# 1750_master.net
KiCad netlist of a schematic drawn in EAGLE
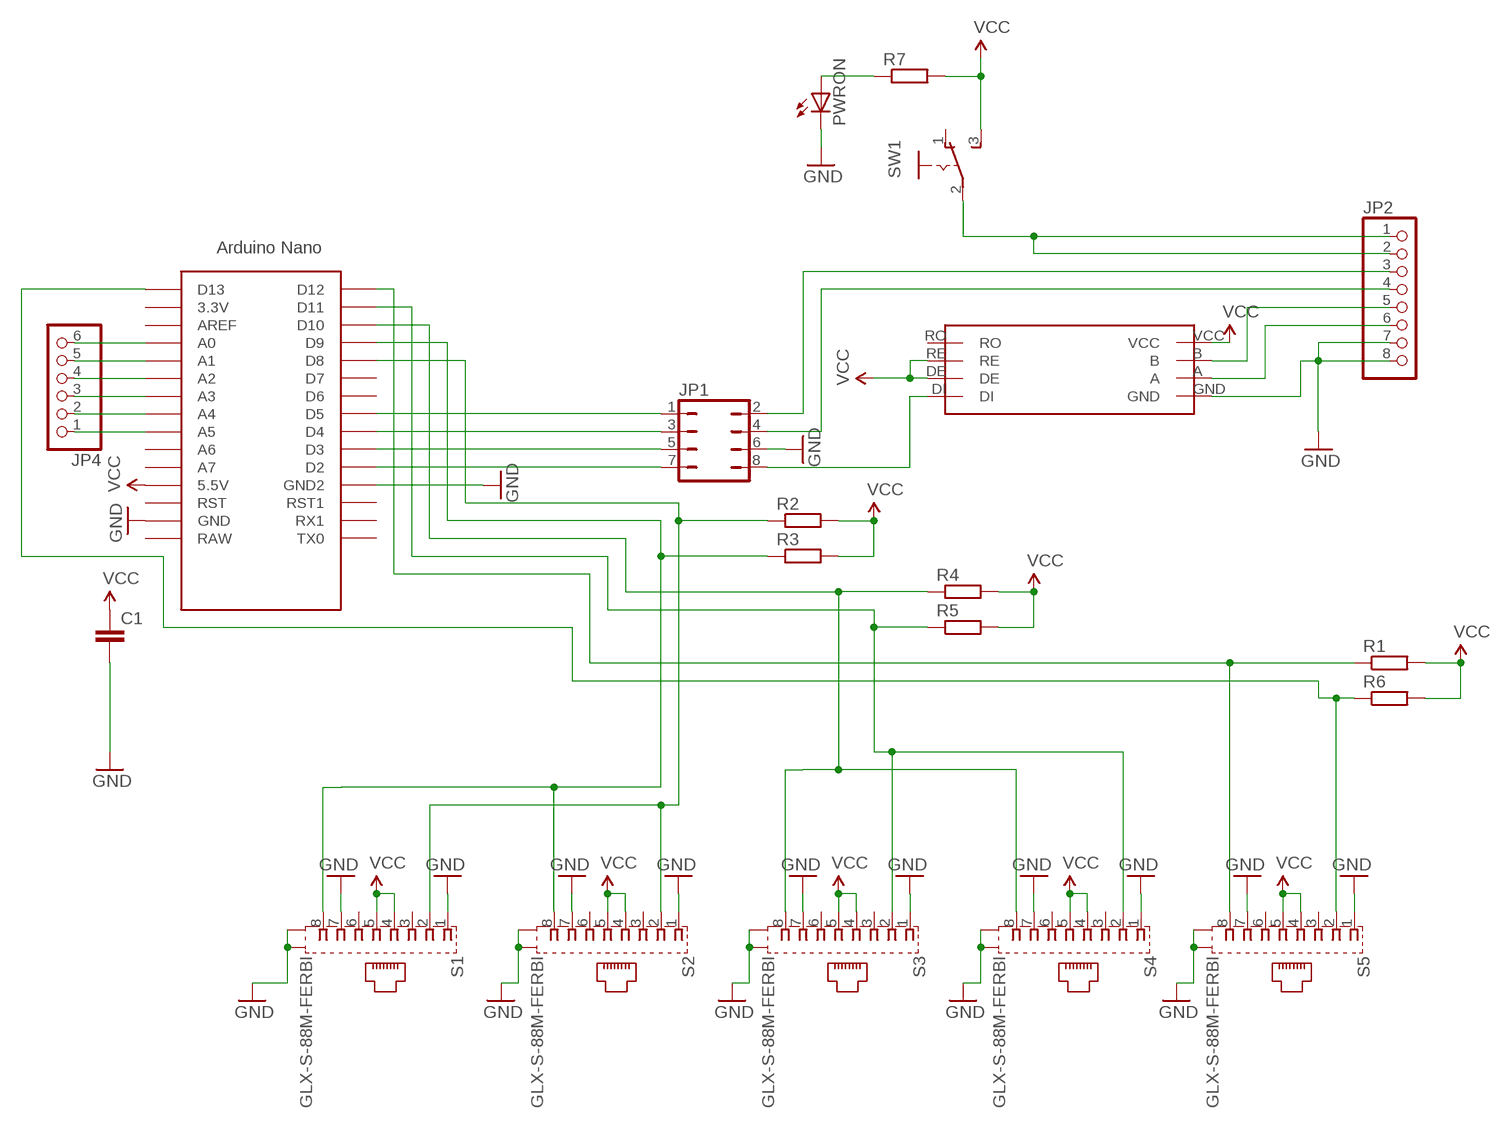
[diagram p0: schematic, sheet 1]

(export (version "E")
  (design (tool "Eeschema 10.0.6"))
  (components
    (comp (ref "C1")
      (value "C-EU025-025X050")
      (footprint "eagle-import:C025-025X050")
      (libsource (lib "eagle-import") (part "C-EU025-025X050"))
    )
    (comp (ref "JP1")
      (value "JP4Q")
      (footprint "eagle-import:JP4Q")
      (libsource (lib "eagle-import") (part "JP4Q"))
    )
    (comp (ref "JP2")
      (value "PINHD-1X8")
      (footprint "eagle-import:1X08")
      (libsource (lib "eagle-import") (part "PINHD-1X8"))
    )
    (comp (ref "JP4")
      (value "PINHD-1X6")
      (footprint "eagle-import:1X06")
      (libsource (lib "eagle-import") (part "PINHD-1X6"))
    )
    (comp (ref "PWRON")
      (value "LED5MM")
      (footprint "eagle-import:LED5MM")
      (libsource (lib "eagle-import") (part "LED5MM"))
    )
    (comp (ref "R1")
      (value "R-EU_0207/10")
      (footprint "eagle-import:0207_10")
      (libsource (lib "eagle-import") (part "R-EU_0207/10"))
    )
    (comp (ref "R2")
      (value "R-EU_0207/10")
      (footprint "eagle-import:0207_10")
      (libsource (lib "eagle-import") (part "R-EU_0207/10"))
    )
    (comp (ref "R3")
      (value "R-EU_0207/10")
      (footprint "eagle-import:0207_10")
      (libsource (lib "eagle-import") (part "R-EU_0207/10"))
    )
    (comp (ref "R4")
      (value "R-EU_0207/10")
      (footprint "eagle-import:0207_10")
      (libsource (lib "eagle-import") (part "R-EU_0207/10"))
    )
    (comp (ref "R5")
      (value "R-EU_0207/10")
      (footprint "eagle-import:0207_10")
      (libsource (lib "eagle-import") (part "R-EU_0207/10"))
    )
    (comp (ref "R6")
      (value "R-EU_0207/10")
      (footprint "eagle-import:0207_10")
      (libsource (lib "eagle-import") (part "R-EU_0207/10"))
    )
    (comp (ref "R7")
      (value "R-EU_0207/10")
      (footprint "eagle-import:0207_10")
      (libsource (lib "eagle-import") (part "R-EU_0207/10"))
    )
    (comp (ref "S1")
      (value "GLX-S-88M-FERBI")
      (footprint "eagle-import:GLX-S-88M-FERBI")
      (libsource (lib "eagle-import") (part "GLX-S-88M-FERBI"))
    )
    (comp (ref "S2")
      (value "GLX-S-88M-FERBI")
      (footprint "eagle-import:GLX-S-88M-FERBI")
      (libsource (lib "eagle-import") (part "GLX-S-88M-FERBI"))
    )
    (comp (ref "S3")
      (value "GLX-S-88M-FERBI")
      (footprint "eagle-import:GLX-S-88M-FERBI")
      (libsource (lib "eagle-import") (part "GLX-S-88M-FERBI"))
    )
    (comp (ref "S4")
      (value "GLX-S-88M-FERBI")
      (footprint "eagle-import:GLX-S-88M-FERBI")
      (libsource (lib "eagle-import") (part "GLX-S-88M-FERBI"))
    )
    (comp (ref "S5")
      (value "GLX-S-88M-FERBI")
      (footprint "eagle-import:GLX-S-88M-FERBI")
      (libsource (lib "eagle-import") (part "GLX-S-88M-FERBI"))
    )
    (comp (ref "SW1")
      (value "255SB")
      (footprint "eagle-import:255SB")
      (libsource (lib "eagle-import") (part "255SB"))
    )
    (comp (ref "U$1")
      (value "NANOF")
      (footprint "eagle-import:NANOF")
      (libsource (lib "eagle-import") (part "NANOF"))
    )
    (comp (ref "U$2")
      (value "485F")
      (footprint "eagle-import:485F")
      (libsource (lib "eagle-import") (part "485F"))
    )
  )
  (nets
    (net (code "1") (name "GND") (class "Default")
      (node (ref "C1") (pin "2") (pinfunction "2_2") (pintype "passive"))
      (node (ref "JP1") (pin "6") (pinfunction "6_6") (pintype "passive"))
      (node (ref "JP2") (pin "7") (pinfunction "7_7") (pintype "passive"))
      (node (ref "JP2") (pin "8") (pinfunction "8_8") (pintype "passive"))
      (node (ref "PWRON") (pin "K") (pinfunction "C_K") (pintype "passive"))
      (node (ref "S1") (pin "1") (pinfunction "1_1") (pintype "passive"))
      (node (ref "S1") (pin "7") (pinfunction "7_7") (pintype "passive"))
      (node (ref "S1") (pin "S1") (pinfunction "S1_S1") (pintype "passive"))
      (node (ref "S1") (pin "S2") (pinfunction "S2_S2") (pintype "passive"))
      (node (ref "S2") (pin "1") (pinfunction "1_1") (pintype "passive"))
      (node (ref "S2") (pin "7") (pinfunction "7_7") (pintype "passive"))
      (node (ref "S2") (pin "S1") (pinfunction "S1_S1") (pintype "passive"))
      (node (ref "S2") (pin "S2") (pinfunction "S2_S2") (pintype "passive"))
      (node (ref "S3") (pin "1") (pinfunction "1_1") (pintype "passive"))
      (node (ref "S3") (pin "7") (pinfunction "7_7") (pintype "passive"))
      (node (ref "S3") (pin "S1") (pinfunction "S1_S1") (pintype "passive"))
      (node (ref "S3") (pin "S2") (pinfunction "S2_S2") (pintype "passive"))
      (node (ref "S4") (pin "1") (pinfunction "1_1") (pintype "passive"))
      (node (ref "S4") (pin "7") (pinfunction "7_7") (pintype "passive"))
      (node (ref "S4") (pin "S1") (pinfunction "S1_S1") (pintype "passive"))
      (node (ref "S4") (pin "S2") (pinfunction "S2_S2") (pintype "passive"))
      (node (ref "S5") (pin "1") (pinfunction "1_1") (pintype "passive"))
      (node (ref "S5") (pin "7") (pinfunction "7_7") (pintype "passive"))
      (node (ref "S5") (pin "S1") (pinfunction "S1_S1") (pintype "passive"))
      (node (ref "S5") (pin "S2") (pinfunction "S2_S2") (pintype "passive"))
      (node (ref "U$1") (pin "GND") (pinfunction "GND_GND") (pintype "bidirectional"))
      (node (ref "U$1") (pin "GND1") (pinfunction "GND2_GND1") (pintype "bidirectional"))
      (node (ref "U$2") (pin "GND") (pinfunction "GND_GND") (pintype "power_in"))
    )
    (net (code "2") (name "Net-(JP1-Pad1)") (class "Default")
      (node (ref "JP1") (pin "1") (pinfunction "1_1") (pintype "passive"))
      (node (ref "U$1") (pin "D5") (pinfunction "D5_D5") (pintype "bidirectional"))
    )
    (net (code "3") (name "Net-(JP1-Pad2)") (class "Default")
      (node (ref "JP1") (pin "2") (pinfunction "2_2") (pintype "passive"))
      (node (ref "JP2") (pin "3") (pinfunction "3_3") (pintype "passive"))
    )
    (net (code "4") (name "Net-(JP1-Pad3)") (class "Default")
      (node (ref "JP1") (pin "3") (pinfunction "3_3") (pintype "passive"))
      (node (ref "U$1") (pin "D4") (pinfunction "D4_D4") (pintype "bidirectional"))
    )
    (net (code "5") (name "Net-(JP1-Pad4)") (class "Default")
      (node (ref "JP1") (pin "4") (pinfunction "4_4") (pintype "passive"))
      (node (ref "JP2") (pin "4") (pinfunction "4_4") (pintype "passive"))
    )
    (net (code "6") (name "Net-(JP1-Pad5)") (class "Default")
      (node (ref "JP1") (pin "5") (pinfunction "5_5") (pintype "passive"))
      (node (ref "U$1") (pin "D3") (pinfunction "D3_D3") (pintype "bidirectional"))
    )
    (net (code "7") (name "Net-(JP1-Pad7)") (class "Default")
      (node (ref "JP1") (pin "7") (pinfunction "7_7") (pintype "passive"))
      (node (ref "U$1") (pin "D2") (pinfunction "D2_D2") (pintype "bidirectional"))
    )
    (net (code "8") (name "Net-(JP1-Pad8)") (class "Default")
      (node (ref "JP1") (pin "8") (pinfunction "8_8") (pintype "passive"))
      (node (ref "U$2") (pin "DI") (pinfunction "DI_DI") (pintype "bidirectional"))
    )
    (net (code "9") (name "Net-(JP2-Pad5)") (class "Default")
      (node (ref "JP2") (pin "5") (pinfunction "5_5") (pintype "passive"))
      (node (ref "U$2") (pin "B") (pinfunction "B_B") (pintype "bidirectional"))
    )
    (net (code "10") (name "Net-(JP2-Pad6)") (class "Default")
      (node (ref "JP2") (pin "6") (pinfunction "6_6") (pintype "passive"))
      (node (ref "U$2") (pin "A") (pinfunction "A_A") (pintype "bidirectional"))
    )
    (net (code "11") (name "Net-(JP4-Pad1)") (class "Default")
      (node (ref "JP4") (pin "1") (pinfunction "1_1") (pintype "passive"))
      (node (ref "U$1") (pin "A5") (pinfunction "A5_A5") (pintype "bidirectional"))
    )
    (net (code "12") (name "Net-(JP4-Pad2)") (class "Default")
      (node (ref "JP4") (pin "2") (pinfunction "2_2") (pintype "passive"))
      (node (ref "U$1") (pin "A4") (pinfunction "A4_A4") (pintype "bidirectional"))
    )
    (net (code "13") (name "Net-(JP4-Pad3)") (class "Default")
      (node (ref "JP4") (pin "3") (pinfunction "3_3") (pintype "passive"))
      (node (ref "U$1") (pin "A3") (pinfunction "A3_A3") (pintype "bidirectional"))
    )
    (net (code "14") (name "Net-(JP4-Pad4)") (class "Default")
      (node (ref "JP4") (pin "4") (pinfunction "4_4") (pintype "passive"))
      (node (ref "U$1") (pin "A2") (pinfunction "A2_A2") (pintype "bidirectional"))
    )
    (net (code "15") (name "Net-(JP4-Pad5)") (class "Default")
      (node (ref "JP4") (pin "5") (pinfunction "5_5") (pintype "passive"))
      (node (ref "U$1") (pin "A1") (pinfunction "A1_A1") (pintype "bidirectional"))
    )
    (net (code "16") (name "Net-(JP4-Pad6)") (class "Default")
      (node (ref "JP4") (pin "6") (pinfunction "6_6") (pintype "passive"))
      (node (ref "U$1") (pin "A0") (pinfunction "A0_A0") (pintype "bidirectional"))
    )
    (net (code "17") (name "Net-(PWRON-PadA)") (class "Default")
      (node (ref "PWRON") (pin "A") (pinfunction "A_A") (pintype "passive"))
      (node (ref "R7") (pin "1") (pinfunction "1_1") (pintype "passive"))
    )
    (net (code "18") (name "Net-(R1-Pad1)") (class "Default")
      (node (ref "R1") (pin "1") (pinfunction "1_1") (pintype "passive"))
      (node (ref "S5") (pin "8") (pinfunction "8_8") (pintype "passive"))
      (node (ref "U$1") (pin "D12") (pinfunction "D12_D12") (pintype "bidirectional"))
    )
    (net (code "19") (name "Net-(R2-Pad1)") (class "Default")
      (node (ref "R2") (pin "1") (pinfunction "1_1") (pintype "passive"))
      (node (ref "S1") (pin "2") (pinfunction "2_2") (pintype "passive"))
      (node (ref "S2") (pin "2") (pinfunction "2_2") (pintype "passive"))
      (node (ref "U$1") (pin "D8") (pinfunction "D8_D8") (pintype "bidirectional"))
    )
    (net (code "20") (name "Net-(R3-Pad1)") (class "Default")
      (node (ref "R3") (pin "1") (pinfunction "1_1") (pintype "passive"))
      (node (ref "S1") (pin "8") (pinfunction "8_8") (pintype "passive"))
      (node (ref "S2") (pin "8") (pinfunction "8_8") (pintype "passive"))
      (node (ref "U$1") (pin "D9") (pinfunction "D9_D9") (pintype "bidirectional"))
    )
    (net (code "21") (name "Net-(R4-Pad1)") (class "Default")
      (node (ref "R4") (pin "1") (pinfunction "1_1") (pintype "passive"))
      (node (ref "S3") (pin "8") (pinfunction "8_8") (pintype "passive"))
      (node (ref "S4") (pin "8") (pinfunction "8_8") (pintype "passive"))
      (node (ref "U$1") (pin "D10") (pinfunction "D10_D10") (pintype "bidirectional"))
    )
    (net (code "22") (name "Net-(R5-Pad1)") (class "Default")
      (node (ref "R5") (pin "1") (pinfunction "1_1") (pintype "passive"))
      (node (ref "S3") (pin "2") (pinfunction "2_2") (pintype "passive"))
      (node (ref "S4") (pin "2") (pinfunction "2_2") (pintype "passive"))
      (node (ref "U$1") (pin "D11") (pinfunction "D11_D11") (pintype "bidirectional"))
    )
    (net (code "23") (name "Net-(R6-Pad1)") (class "Default")
      (node (ref "R6") (pin "1") (pinfunction "1_1") (pintype "passive"))
      (node (ref "S5") (pin "2") (pinfunction "2_2") (pintype "passive"))
      (node (ref "U$1") (pin "D13") (pinfunction "D13_D13") (pintype "bidirectional"))
    )
    (net (code "24") (name "Net-(SW1-P)") (class "Default")
      (node (ref "JP2") (pin "1") (pinfunction "1_1") (pintype "passive"))
      (node (ref "JP2") (pin "2") (pinfunction "2_2") (pintype "passive"))
      (node (ref "SW1") (pin "2") (pinfunction "P_2") (pintype "passive"))
    )
    (net (code "25") (name "VCC") (class "Default")
      (node (ref "C1") (pin "1") (pinfunction "1_1") (pintype "passive"))
      (node (ref "R1") (pin "2") (pinfunction "2_2") (pintype "passive"))
      (node (ref "R2") (pin "2") (pinfunction "2_2") (pintype "passive"))
      (node (ref "R3") (pin "2") (pinfunction "2_2") (pintype "passive"))
      (node (ref "R4") (pin "2") (pinfunction "2_2") (pintype "passive"))
      (node (ref "R5") (pin "2") (pinfunction "2_2") (pintype "passive"))
      (node (ref "R6") (pin "2") (pinfunction "2_2") (pintype "passive"))
      (node (ref "R7") (pin "2") (pinfunction "2_2") (pintype "passive"))
      (node (ref "S1") (pin "4") (pinfunction "4_4") (pintype "passive"))
      (node (ref "S1") (pin "5") (pinfunction "5_5") (pintype "passive"))
      (node (ref "S2") (pin "4") (pinfunction "4_4") (pintype "passive"))
      (node (ref "S2") (pin "5") (pinfunction "5_5") (pintype "passive"))
      (node (ref "S3") (pin "4") (pinfunction "4_4") (pintype "passive"))
      (node (ref "S3") (pin "5") (pinfunction "5_5") (pintype "passive"))
      (node (ref "S4") (pin "4") (pinfunction "4_4") (pintype "passive"))
      (node (ref "S4") (pin "5") (pinfunction "5_5") (pintype "passive"))
      (node (ref "S5") (pin "4") (pinfunction "4_4") (pintype "passive"))
      (node (ref "S5") (pin "5") (pinfunction "5_5") (pintype "passive"))
      (node (ref "SW1") (pin "3") (pinfunction "S_3") (pintype "passive"))
      (node (ref "U$1") (pin "5V") (pinfunction "5.5V_5V") (pintype "bidirectional"))
      (node (ref "U$2") (pin "DE") (pinfunction "DE_DE") (pintype "bidirectional"))
      (node (ref "U$2") (pin "RE") (pinfunction "RE_RE") (pintype "bidirectional"))
      (node (ref "U$2") (pin "VCC") (pinfunction "VCC_VCC") (pintype "power_in"))
    )
    (net (code "26") (name "unconnected-(S1-Pad3)") (class "Default")
      (node (ref "S1") (pin "3") (pinfunction "3_3") (pintype "passive"))
    )
    (net (code "27") (name "unconnected-(S1-Pad6)") (class "Default")
      (node (ref "S1") (pin "6") (pinfunction "6_6") (pintype "passive"))
    )
    (net (code "28") (name "unconnected-(S2-Pad3)") (class "Default")
      (node (ref "S2") (pin "3") (pinfunction "3_3") (pintype "passive"))
    )
    (net (code "29") (name "unconnected-(S2-Pad6)") (class "Default")
      (node (ref "S2") (pin "6") (pinfunction "6_6") (pintype "passive"))
    )
    (net (code "30") (name "unconnected-(S3-Pad3)") (class "Default")
      (node (ref "S3") (pin "3") (pinfunction "3_3") (pintype "passive"))
    )
    (net (code "31") (name "unconnected-(S3-Pad6)") (class "Default")
      (node (ref "S3") (pin "6") (pinfunction "6_6") (pintype "passive"))
    )
    (net (code "32") (name "unconnected-(S4-Pad3)") (class "Default")
      (node (ref "S4") (pin "3") (pinfunction "3_3") (pintype "passive"))
    )
    (net (code "33") (name "unconnected-(S4-Pad6)") (class "Default")
      (node (ref "S4") (pin "6") (pinfunction "6_6") (pintype "passive"))
    )
    (net (code "34") (name "unconnected-(S5-Pad3)") (class "Default")
      (node (ref "S5") (pin "3") (pinfunction "3_3") (pintype "passive"))
    )
    (net (code "35") (name "unconnected-(S5-Pad6)") (class "Default")
      (node (ref "S5") (pin "6") (pinfunction "6_6") (pintype "passive"))
    )
    (net (code "36") (name "unconnected-(SW1-O-Pad1)") (class "Default")
      (node (ref "SW1") (pin "1") (pinfunction "O_1") (pintype "passive"))
    )
    (net (code "37") (name "unconnected-(U$1-Pad3.3V)") (class "Default")
      (node (ref "U$1") (pin "3.3V") (pinfunction "3.3V_3.3V") (pintype "bidirectional"))
    )
    (net (code "38") (name "unconnected-(U$1-PadA6)") (class "Default")
      (node (ref "U$1") (pin "A6") (pinfunction "A6_A6") (pintype "bidirectional"))
    )
    (net (code "39") (name "unconnected-(U$1-PadA7)") (class "Default")
      (node (ref "U$1") (pin "A7") (pinfunction "A7_A7") (pintype "bidirectional"))
    )
    (net (code "40") (name "unconnected-(U$1-PadAREF)") (class "Default")
      (node (ref "U$1") (pin "AREF") (pinfunction "AREF_AREF") (pintype "bidirectional"))
    )
    (net (code "41") (name "unconnected-(U$1-PadD6)") (class "Default")
      (node (ref "U$1") (pin "D6") (pinfunction "D6_D6") (pintype "bidirectional"))
    )
    (net (code "42") (name "unconnected-(U$1-PadD7)") (class "Default")
      (node (ref "U$1") (pin "D7") (pinfunction "D7_D7") (pintype "bidirectional"))
    )
    (net (code "43") (name "unconnected-(U$1-PadRAW)") (class "Default")
      (node (ref "U$1") (pin "RAW") (pinfunction "RAW_RAW") (pintype "bidirectional"))
    )
    (net (code "44") (name "unconnected-(U$1-PadRST)") (class "Default")
      (node (ref "U$1") (pin "RST") (pinfunction "RST_RST") (pintype "bidirectional"))
    )
    (net (code "45") (name "unconnected-(U$1-PadRST1)") (class "Default")
      (node (ref "U$1") (pin "RST1") (pinfunction "RST1_RST1") (pintype "bidirectional"))
    )
    (net (code "46") (name "unconnected-(U$1-PadRX1)") (class "Default")
      (node (ref "U$1") (pin "RX1") (pinfunction "RX1_RX1") (pintype "bidirectional"))
    )
    (net (code "47") (name "unconnected-(U$1-PadTX0)") (class "Default")
      (node (ref "U$1") (pin "TX0") (pinfunction "TX0_TX0") (pintype "bidirectional"))
    )
    (net (code "48") (name "unconnected-(U$2-PadRO)") (class "Default")
      (node (ref "U$2") (pin "RO") (pinfunction "RO_RO") (pintype "bidirectional"))
    )
  )
)
